# LoRa1278_Breakout.net
KiCad netlist of a schematic drawn in EAGLE
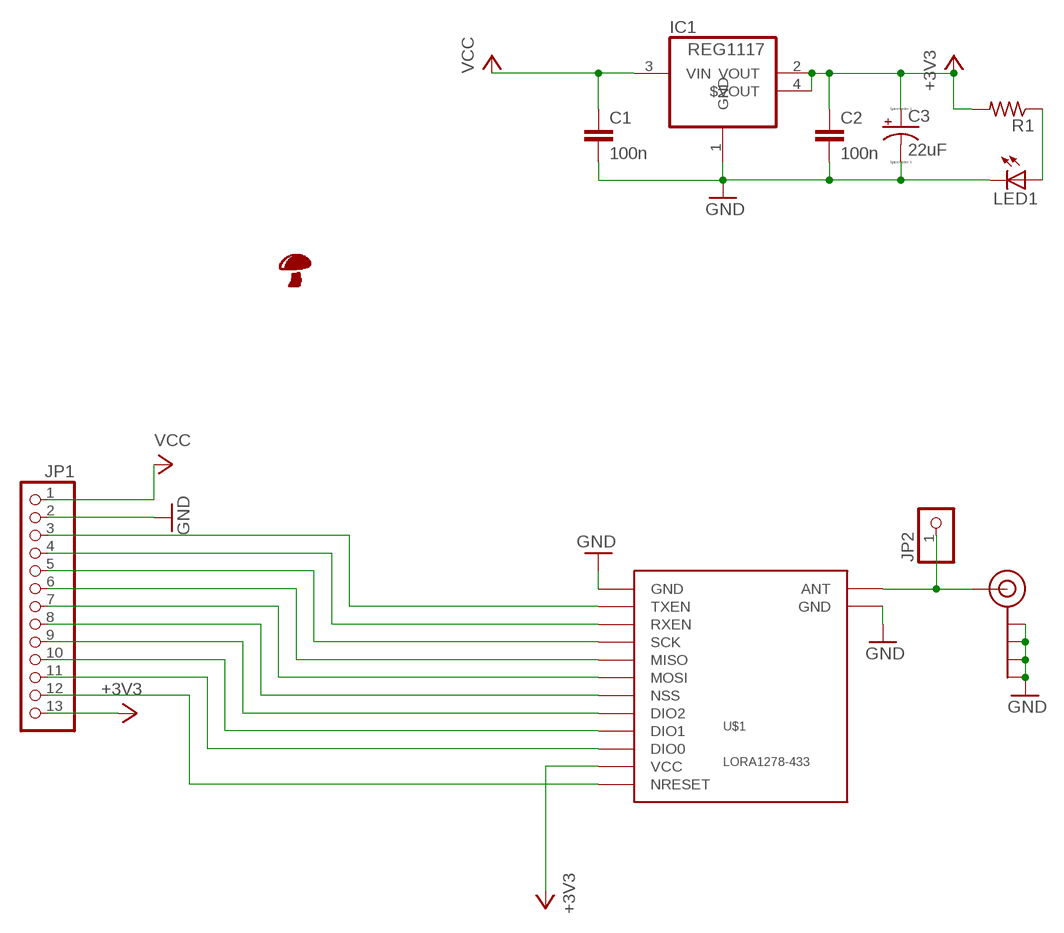
[diagram p0: schematic, sheet 1]

(export (version "E")
  (design (tool "Eeschema 10.0.6"))
  (components
    (comp (ref "C1")
      (value "100n")
      (footprint "eagle-import:C0805")
      (libsource (lib "eagle-import") (part "C-EUC0805"))
    )
    (comp (ref "C2")
      (value "100n")
      (footprint "eagle-import:C0805")
      (libsource (lib "eagle-import") (part "C-EUC0805"))
    )
    (comp (ref "C3")
      (value "22uF")
      (footprint "eagle-import:PANASONIC_C")
      (libsource (lib "eagle-import") (part "CPOL-USC"))
    )
    (comp (ref "IC1")
      (value "REG1117")
      (footprint "eagle-import:SOT223")
      (libsource (lib "eagle-import") (part "REG1117"))
    )
    (comp (ref "J$1")
      (value "SMA_EDGE")
      (footprint "eagle-import:SMA-EDGE")
      (libsource (lib "eagle-import") (part "SMA_EDGE"))
    )
    (comp (ref "JP1")
      (value "PINHD-1X13")
      (footprint "eagle-import:1X13")
      (libsource (lib "eagle-import") (part "PINHD-1X13"))
    )
    (comp (ref "JP2")
      (value "PINHD-1X1")
      (footprint "eagle-import:1X01")
      (libsource (lib "eagle-import") (part "PINHD-1X1"))
    )
    (comp (ref "LED1")
      (value "LEDCHIP-LED0805")
      (footprint "eagle-import:CHIP-LED0805")
      (libsource (lib "eagle-import") (part "LEDCHIP-LED0805"))
    )
    (comp (ref "R1")
      (value "R-US_R0805")
      (footprint "eagle-import:R0805")
      (libsource (lib "eagle-import") (part "R-US_R0805"))
    )
    (comp (ref "U$1")
      (value "LORA1278-433")
      (footprint "eagle-import:LORA1278")
      (libsource (lib "eagle-import") (part "LORA1278-433"))
    )
    (comp (ref "U$2")
      (value "SHROOM5MM")
      (footprint "eagle-import:SHROOM")
      (libsource (lib "eagle-import") (part "SHROOM5MM"))
    )
  )
  (nets
    (net (code "1") (name "+3V3") (class "Default")
      (node (ref "C2") (pin "1") (pinfunction "1_1") (pintype "passive"))
      (node (ref "C3") (pin "+") (pinfunction "+_+") (pintype "passive"))
      (node (ref "IC1") (pin "2") (pinfunction "VOUT_2") (pintype "output"))
      (node (ref "IC1") (pin "4") (pinfunction "$VOUT_4") (pintype "output"))
      (node (ref "JP1") (pin "13") (pinfunction "13_13") (pintype "passive"))
      (node (ref "R1") (pin "2") (pinfunction "2_2") (pintype "passive"))
      (node (ref "U$1") (pin "P$11") (pinfunction "VCC_P$11") (pintype "power_in"))
    )
    (net (code "2") (name "GND") (class "Default")
      (node (ref "C1") (pin "2") (pinfunction "2_2") (pintype "passive"))
      (node (ref "C2") (pin "2") (pinfunction "2_2") (pintype "passive"))
      (node (ref "C3") (pin "-") (pinfunction "-_-") (pintype "passive"))
      (node (ref "IC1") (pin "1") (pinfunction "GND_1") (pintype "power_in"))
      (node (ref "J$1") (pin "GND@0") (pinfunction "GND_GND@0") (pintype "bidirectional"))
      (node (ref "J$1") (pin "GND@1") (pinfunction "GND_GND@1") (pintype "bidirectional"))
      (node (ref "J$1") (pin "GND@2") (pinfunction "GND_GND@2") (pintype "bidirectional"))
      (node (ref "J$1") (pin "GND@3") (pinfunction "GND_GND@3") (pintype "bidirectional"))
      (node (ref "JP1") (pin "2") (pinfunction "2_2") (pintype "passive"))
      (node (ref "LED1") (pin "C") (pinfunction "C_C") (pintype "passive"))
      (node (ref "U$1") (pin "P$1") (pinfunction "GND_P$1") (pintype "power_in"))
      (node (ref "U$1") (pin "P$14") (pinfunction "GND_P$14") (pintype "power_in"))
    )
    (net (code "3") (name "Net-(J$1-SIGNAL)") (class "Default")
      (node (ref "J$1") (pin "SIG") (pinfunction "SIGNAL_SIG") (pintype "bidirectional"))
      (node (ref "JP2") (pin "1") (pinfunction "1_1") (pintype "passive"))
      (node (ref "U$1") (pin "P$13") (pinfunction "ANT_P$13") (pintype "bidirectional"))
    )
    (net (code "4") (name "Net-(LED1-PadA)") (class "Default")
      (node (ref "LED1") (pin "A") (pinfunction "A_A") (pintype "passive"))
      (node (ref "R1") (pin "1") (pinfunction "1_1") (pintype "passive"))
    )
    (net (code "5") (name "Net-(U$1-DIO0)") (class "Default")
      (node (ref "JP1") (pin "11") (pinfunction "11_11") (pintype "passive"))
      (node (ref "U$1") (pin "P$10") (pinfunction "DIO0_P$10") (pintype "bidirectional"))
    )
    (net (code "6") (name "Net-(U$1-DIO1)") (class "Default")
      (node (ref "JP1") (pin "10") (pinfunction "10_10") (pintype "passive"))
      (node (ref "U$1") (pin "P$9") (pinfunction "DIO1_P$9") (pintype "bidirectional"))
    )
    (net (code "7") (name "Net-(U$1-DIO2)") (class "Default")
      (node (ref "JP1") (pin "9") (pinfunction "9_9") (pintype "passive"))
      (node (ref "U$1") (pin "P$8") (pinfunction "DIO2_P$8") (pintype "bidirectional"))
    )
    (net (code "8") (name "Net-(U$1-MISO)") (class "Default")
      (node (ref "JP1") (pin "6") (pinfunction "6_6") (pintype "passive"))
      (node (ref "U$1") (pin "P$5") (pinfunction "MISO_P$5") (pintype "bidirectional"))
    )
    (net (code "9") (name "Net-(U$1-MOSI)") (class "Default")
      (node (ref "JP1") (pin "7") (pinfunction "7_7") (pintype "passive"))
      (node (ref "U$1") (pin "P$6") (pinfunction "MOSI_P$6") (pintype "bidirectional"))
    )
    (net (code "10") (name "Net-(U$1-NRESET)") (class "Default")
      (node (ref "JP1") (pin "12") (pinfunction "12_12") (pintype "passive"))
      (node (ref "U$1") (pin "P$12") (pinfunction "NRESET_P$12") (pintype "bidirectional"))
    )
    (net (code "11") (name "Net-(U$1-NSS)") (class "Default")
      (node (ref "JP1") (pin "8") (pinfunction "8_8") (pintype "passive"))
      (node (ref "U$1") (pin "P$7") (pinfunction "NSS_P$7") (pintype "bidirectional"))
    )
    (net (code "12") (name "Net-(U$1-RXEN)") (class "Default")
      (node (ref "JP1") (pin "4") (pinfunction "4_4") (pintype "passive"))
      (node (ref "U$1") (pin "P$3") (pinfunction "RXEN_P$3") (pintype "bidirectional"))
    )
    (net (code "13") (name "Net-(U$1-SCK)") (class "Default")
      (node (ref "JP1") (pin "5") (pinfunction "5_5") (pintype "passive"))
      (node (ref "U$1") (pin "P$4") (pinfunction "SCK_P$4") (pintype "bidirectional"))
    )
    (net (code "14") (name "Net-(U$1-TXEN)") (class "Default")
      (node (ref "JP1") (pin "3") (pinfunction "3_3") (pintype "passive"))
      (node (ref "U$1") (pin "P$2") (pinfunction "TXEN_P$2") (pintype "bidirectional"))
    )
    (net (code "15") (name "VCC") (class "Default")
      (node (ref "C1") (pin "1") (pinfunction "1_1") (pintype "passive"))
      (node (ref "IC1") (pin "3") (pinfunction "VIN_3") (pintype "input"))
      (node (ref "JP1") (pin "1") (pinfunction "1_1") (pintype "passive"))
    )
  )
)
